# iso.net
KiCad netlist of a schematic drawn in EasyEDA Pro
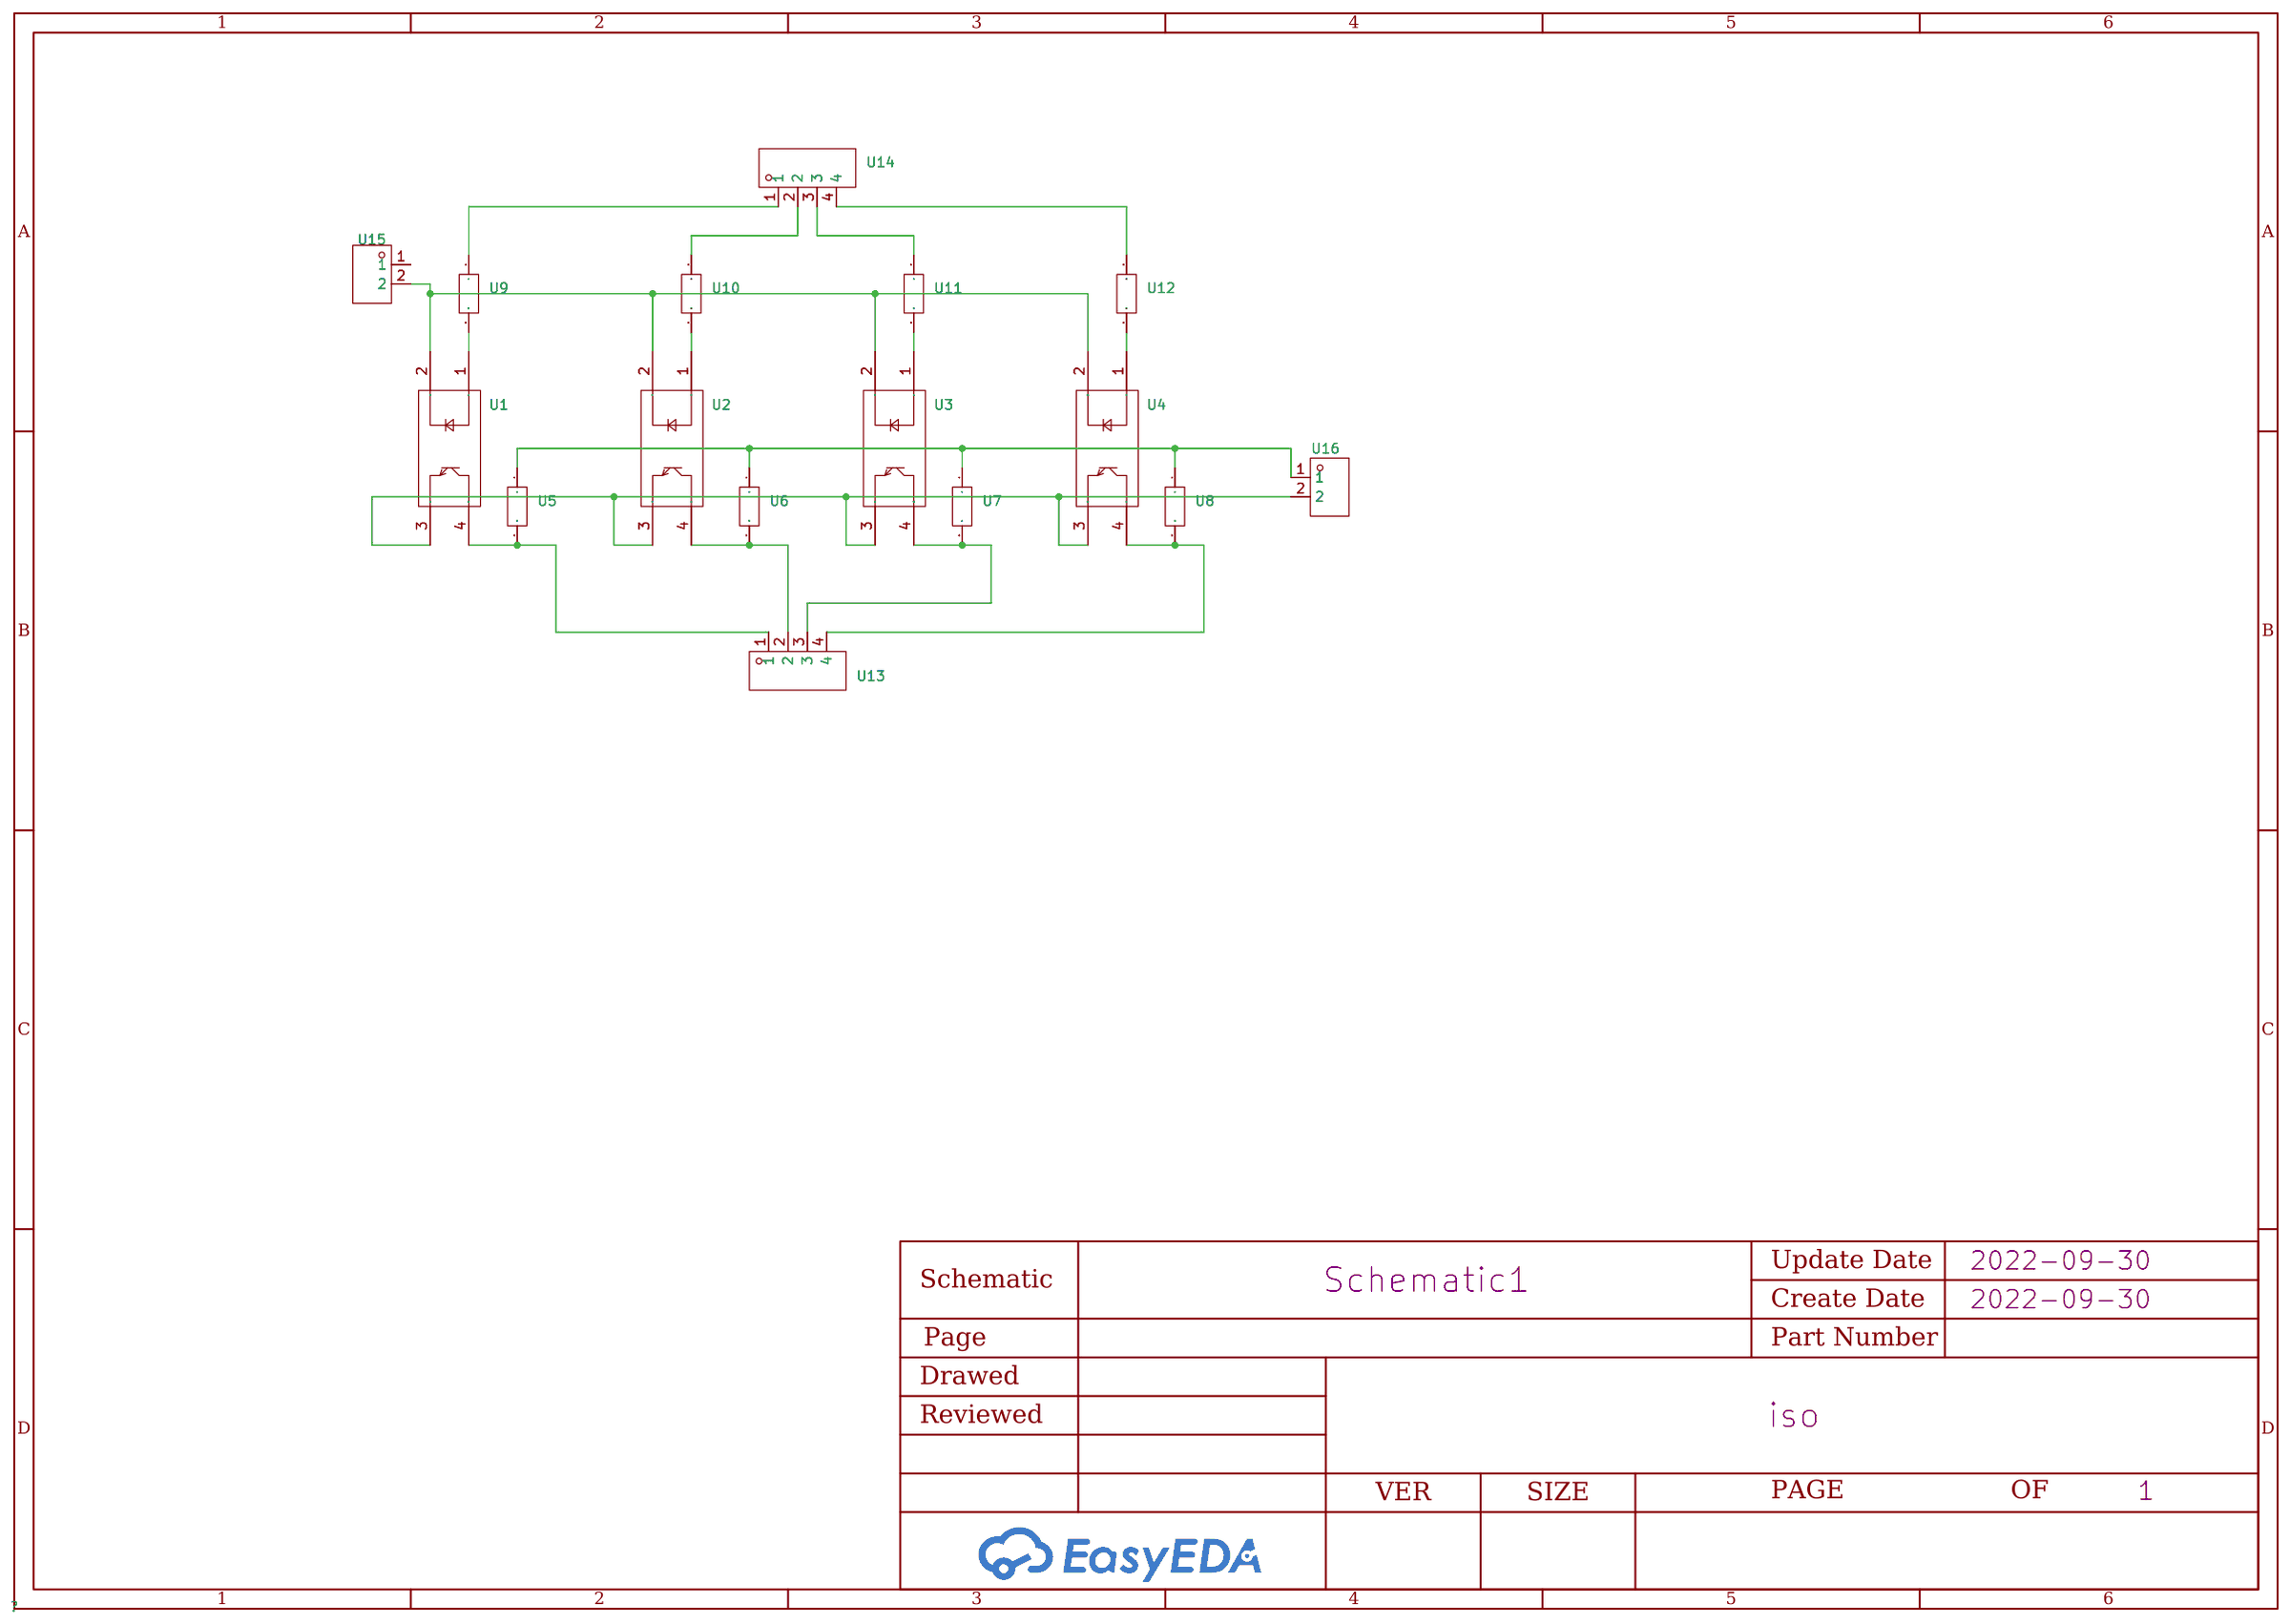
[diagram p0: schematic sheet]

(export (version "E")
  (design (tool "Eeschema 10.0.6"))
  (components
    (comp (ref "U1")
      (value "~")
      (footprint "easyedapro:DIP-4_L4.6-W6.5-P2.54-LS7.6-BL")
      (fields (field (name "Manufacturer Part") "UPC817AG-D04-T") (field (name "Manufacturer") "UTC(友顺)"))
      (libsource (lib "easyedapro") (part "UPC817AG-D04-T"))
    )
    (comp (ref "U2")
      (value "~")
      (footprint "easyedapro:DIP-4_L4.6-W6.5-P2.54-LS7.6-BL")
      (fields (field (name "Manufacturer Part") "UPC817AG-D04-T") (field (name "Manufacturer") "UTC(友顺)"))
      (libsource (lib "easyedapro") (part "UPC817AG-D04-T"))
    )
    (comp (ref "U3")
      (value "~")
      (footprint "easyedapro:DIP-4_L4.6-W6.5-P2.54-LS7.6-BL")
      (fields (field (name "Manufacturer Part") "UPC817AG-D04-T") (field (name "Manufacturer") "UTC(友顺)"))
      (libsource (lib "easyedapro") (part "UPC817AG-D04-T"))
    )
    (comp (ref "U4")
      (value "~")
      (footprint "easyedapro:DIP-4_L4.6-W6.5-P2.54-LS7.6-BL")
      (fields (field (name "Manufacturer Part") "UPC817AG-D04-T") (field (name "Manufacturer") "UTC(友顺)"))
      (libsource (lib "easyedapro") (part "UPC817AG-D04-T"))
    )
    (comp (ref "U5")
      (value "~")
      (footprint "easyedapro:RES-TH_12R_2W")
      (fields
        (field (name "Manufacturer Part") "Resistor_THT:R_Axial_DIN0309_L9.0mm_D3.2mm_P2.54mm_Vertical")
      )
      (libsource (lib "easyedapro") (part "RESISTOR_THT{colon}R_AXIAL_DIN0309_L9.0MM_D3.2MM_P2.54MM_VERTICAL"))
    )
    (comp (ref "U6")
      (value "~")
      (footprint "easyedapro:RES-TH_12R_2W")
      (fields
        (field (name "Manufacturer Part") "Resistor_THT:R_Axial_DIN0309_L9.0mm_D3.2mm_P2.54mm_Vertical")
      )
      (libsource (lib "easyedapro") (part "RESISTOR_THT{colon}R_AXIAL_DIN0309_L9.0MM_D3.2MM_P2.54MM_VERTICAL"))
    )
    (comp (ref "U7")
      (value "~")
      (footprint "easyedapro:RES-TH_12R_2W")
      (fields
        (field (name "Manufacturer Part") "Resistor_THT:R_Axial_DIN0309_L9.0mm_D3.2mm_P2.54mm_Vertical")
      )
      (libsource (lib "easyedapro") (part "RESISTOR_THT{colon}R_AXIAL_DIN0309_L9.0MM_D3.2MM_P2.54MM_VERTICAL"))
    )
    (comp (ref "U8")
      (value "~")
      (footprint "easyedapro:RES-TH_12R_2W")
      (fields
        (field (name "Manufacturer Part") "Resistor_THT:R_Axial_DIN0309_L9.0mm_D3.2mm_P2.54mm_Vertical")
      )
      (libsource (lib "easyedapro") (part "RESISTOR_THT{colon}R_AXIAL_DIN0309_L9.0MM_D3.2MM_P2.54MM_VERTICAL"))
    )
    (comp (ref "U9")
      (value "~")
      (footprint "easyedapro:RES-TH_12R_2W")
      (fields
        (field (name "Manufacturer Part") "Resistor_THT:R_Axial_DIN0309_L9.0mm_D3.2mm_P2.54mm_Vertical")
      )
      (libsource (lib "easyedapro") (part "RESISTOR_THT{colon}R_AXIAL_DIN0309_L9.0MM_D3.2MM_P2.54MM_VERTICAL"))
    )
    (comp (ref "U10")
      (value "~")
      (footprint "easyedapro:RES-TH_12R_2W")
      (fields
        (field (name "Manufacturer Part") "Resistor_THT:R_Axial_DIN0309_L9.0mm_D3.2mm_P2.54mm_Vertical")
      )
      (libsource (lib "easyedapro") (part "RESISTOR_THT{colon}R_AXIAL_DIN0309_L9.0MM_D3.2MM_P2.54MM_VERTICAL"))
    )
    (comp (ref "U11")
      (value "~")
      (footprint "easyedapro:RES-TH_12R_2W")
      (fields
        (field (name "Manufacturer Part") "Resistor_THT:R_Axial_DIN0309_L9.0mm_D3.2mm_P2.54mm_Vertical")
      )
      (libsource (lib "easyedapro") (part "RESISTOR_THT{colon}R_AXIAL_DIN0309_L9.0MM_D3.2MM_P2.54MM_VERTICAL"))
    )
    (comp (ref "U12")
      (value "~")
      (footprint "easyedapro:RES-TH_12R_2W")
      (fields
        (field (name "Manufacturer Part") "Resistor_THT:R_Axial_DIN0309_L9.0mm_D3.2mm_P2.54mm_Vertical")
      )
      (libsource (lib "easyedapro") (part "RESISTOR_THT{colon}R_AXIAL_DIN0309_L9.0MM_D3.2MM_P2.54MM_VERTICAL"))
    )
    (comp (ref "U13")
      (value "~")
      (footprint "easyedapro:CONN-TH_DB125-2.54-4P-GN")
      (fields
        (field (name "Manufacturer Part") "DB125-2.54-4P-GN")
        (field (name "Manufacturer") "DIBO(地博电气)")
      )
      (libsource (lib "easyedapro") (part "DB125-2.54-4P-GN"))
    )
    (comp (ref "U14")
      (value "~")
      (footprint "easyedapro:CONN-TH_DB125-2.54-4P-GN")
      (fields
        (field (name "Manufacturer Part") "DB125-2.54-4P-GN")
        (field (name "Manufacturer") "DIBO(地博电气)")
      )
      (libsource (lib "easyedapro") (part "DB125-2.54-4P-GN"))
    )
    (comp (ref "U15")
      (value "~")
      (footprint "easyedapro:CONN-TH_DB125-2.54-2P-GN")
      (fields
        (field (name "Manufacturer Part") "DB125-2.54-2P-GN")
        (field (name "Manufacturer") "DIBO(地博电气)")
      )
      (libsource (lib "easyedapro") (part "DB125-2.54-2P-GN"))
    )
    (comp (ref "U16")
      (value "~")
      (footprint "easyedapro:CONN-TH_DB125-2.54-2P-GN")
      (fields
        (field (name "Manufacturer Part") "DB125-2.54-2P-GN")
        (field (name "Manufacturer") "DIBO(地博电气)")
      )
      (libsource (lib "easyedapro") (part "DB125-2.54-2P-GN"))
    )
  )
  (nets
    (net (code "1") (name "Net-(U1-A)") (class "Default")
      (node (ref "U1") (pin "1") (pinfunction "A_1") (pintype "input"))
      (node (ref "U9") (pin "2") (pinfunction "2_2") (pintype "input"))
    )
    (net (code "2") (name "Net-(U1-C)") (class "Default")
      (node (ref "U1") (pin "2") (pinfunction "C_2") (pintype "input"))
      (node (ref "U15") (pin "2") (pinfunction "2_2") (pintype "input"))
      (node (ref "U2") (pin "2") (pinfunction "C_2") (pintype "input"))
      (node (ref "U3") (pin "2") (pinfunction "C_2") (pintype "input"))
      (node (ref "U4") (pin "2") (pinfunction "C_2") (pintype "input"))
    )
    (net (code "3") (name "Net-(U1-COL)") (class "Default")
      (node (ref "U1") (pin "4") (pinfunction "COL_4") (pintype "input"))
      (node (ref "U13") (pin "1") (pinfunction "1_1") (pintype "input"))
      (node (ref "U5") (pin "2") (pinfunction "2_2") (pintype "input"))
    )
    (net (code "4") (name "Net-(U1-EM)") (class "Default")
      (node (ref "U1") (pin "3") (pinfunction "EM_3") (pintype "input"))
      (node (ref "U16") (pin "2") (pinfunction "2_2") (pintype "input"))
      (node (ref "U2") (pin "3") (pinfunction "EM_3") (pintype "input"))
      (node (ref "U3") (pin "3") (pinfunction "EM_3") (pintype "input"))
      (node (ref "U4") (pin "3") (pinfunction "EM_3") (pintype "input"))
    )
    (net (code "5") (name "Net-(U2-A)") (class "Default")
      (node (ref "U10") (pin "2") (pinfunction "2_2") (pintype "input"))
      (node (ref "U2") (pin "1") (pinfunction "A_1") (pintype "input"))
    )
    (net (code "6") (name "Net-(U2-COL)") (class "Default")
      (node (ref "U13") (pin "2") (pinfunction "2_2") (pintype "input"))
      (node (ref "U2") (pin "4") (pinfunction "COL_4") (pintype "input"))
      (node (ref "U6") (pin "2") (pinfunction "2_2") (pintype "input"))
    )
    (net (code "7") (name "Net-(U3-A)") (class "Default")
      (node (ref "U11") (pin "2") (pinfunction "2_2") (pintype "input"))
      (node (ref "U3") (pin "1") (pinfunction "A_1") (pintype "input"))
    )
    (net (code "8") (name "Net-(U3-COL)") (class "Default")
      (node (ref "U13") (pin "3") (pinfunction "3_3") (pintype "input"))
      (node (ref "U3") (pin "4") (pinfunction "COL_4") (pintype "input"))
      (node (ref "U7") (pin "2") (pinfunction "2_2") (pintype "input"))
    )
    (net (code "9") (name "Net-(U4-A)") (class "Default")
      (node (ref "U12") (pin "2") (pinfunction "2_2") (pintype "input"))
      (node (ref "U4") (pin "1") (pinfunction "A_1") (pintype "input"))
    )
    (net (code "10") (name "Net-(U4-COL)") (class "Default")
      (node (ref "U13") (pin "4") (pinfunction "4_4") (pintype "input"))
      (node (ref "U4") (pin "4") (pinfunction "COL_4") (pintype "input"))
      (node (ref "U8") (pin "2") (pinfunction "2_2") (pintype "input"))
    )
    (net (code "11") (name "Net-(U10-Pad1)") (class "Default")
      (node (ref "U10") (pin "1") (pinfunction "1_1") (pintype "input"))
      (node (ref "U14") (pin "2") (pinfunction "2_2") (pintype "input"))
    )
    (net (code "12") (name "Net-(U11-Pad1)") (class "Default")
      (node (ref "U11") (pin "1") (pinfunction "1_1") (pintype "input"))
      (node (ref "U14") (pin "3") (pinfunction "3_3") (pintype "input"))
    )
    (net (code "13") (name "Net-(U12-Pad1)") (class "Default")
      (node (ref "U12") (pin "1") (pinfunction "1_1") (pintype "input"))
      (node (ref "U14") (pin "4") (pinfunction "4_4") (pintype "input"))
    )
    (net (code "14") (name "Net-(U14-Pad1)") (class "Default")
      (node (ref "U14") (pin "1") (pinfunction "1_1") (pintype "input"))
      (node (ref "U9") (pin "1") (pinfunction "1_1") (pintype "input"))
    )
    (net (code "15") (name "Net-(U16-Pad1)") (class "Default")
      (node (ref "U16") (pin "1") (pinfunction "1_1") (pintype "input"))
      (node (ref "U5") (pin "1") (pinfunction "1_1") (pintype "input"))
      (node (ref "U6") (pin "1") (pinfunction "1_1") (pintype "input"))
      (node (ref "U7") (pin "1") (pinfunction "1_1") (pintype "input"))
      (node (ref "U8") (pin "1") (pinfunction "1_1") (pintype "input"))
    )
    (net (code "16") (name "unconnected-(U15-Pad1)") (class "Default")
      (node (ref "U15") (pin "1") (pinfunction "1_1") (pintype "input"))
    )
  )
)
